# LDA_Board.net
KiCad netlist of a schematic drawn in EAGLE
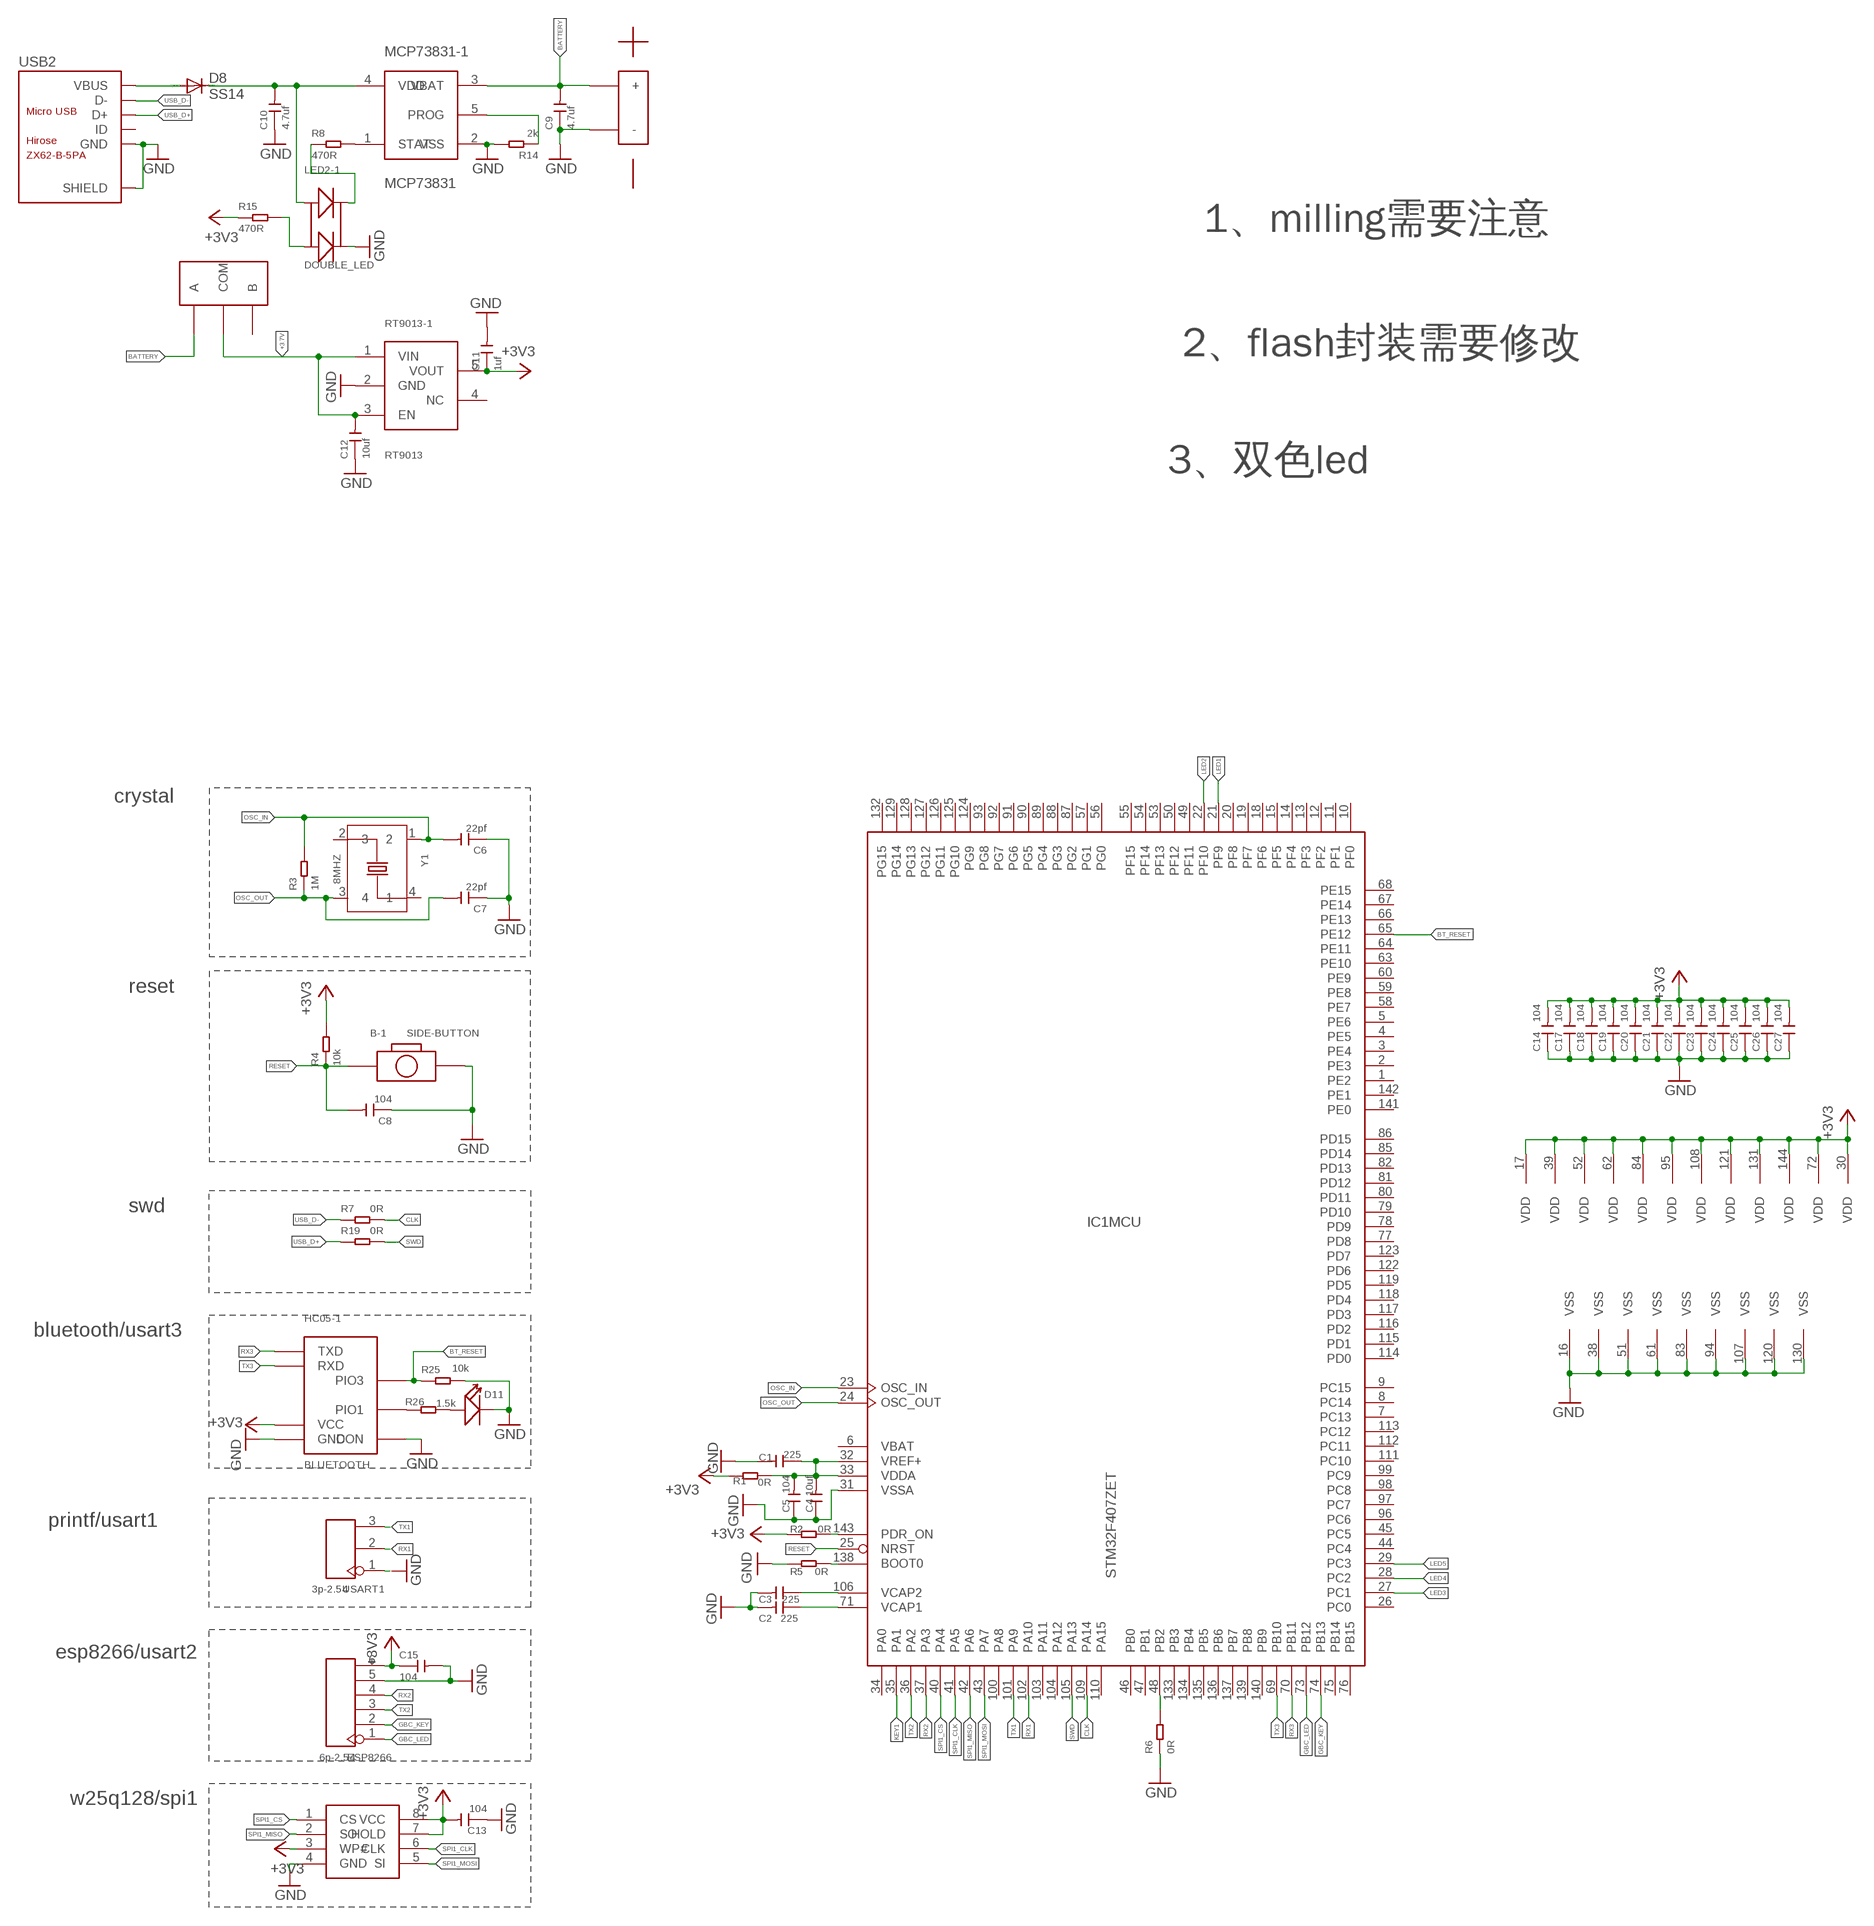
[diagram p0: schematic, sheet 1, part 1 of 2]
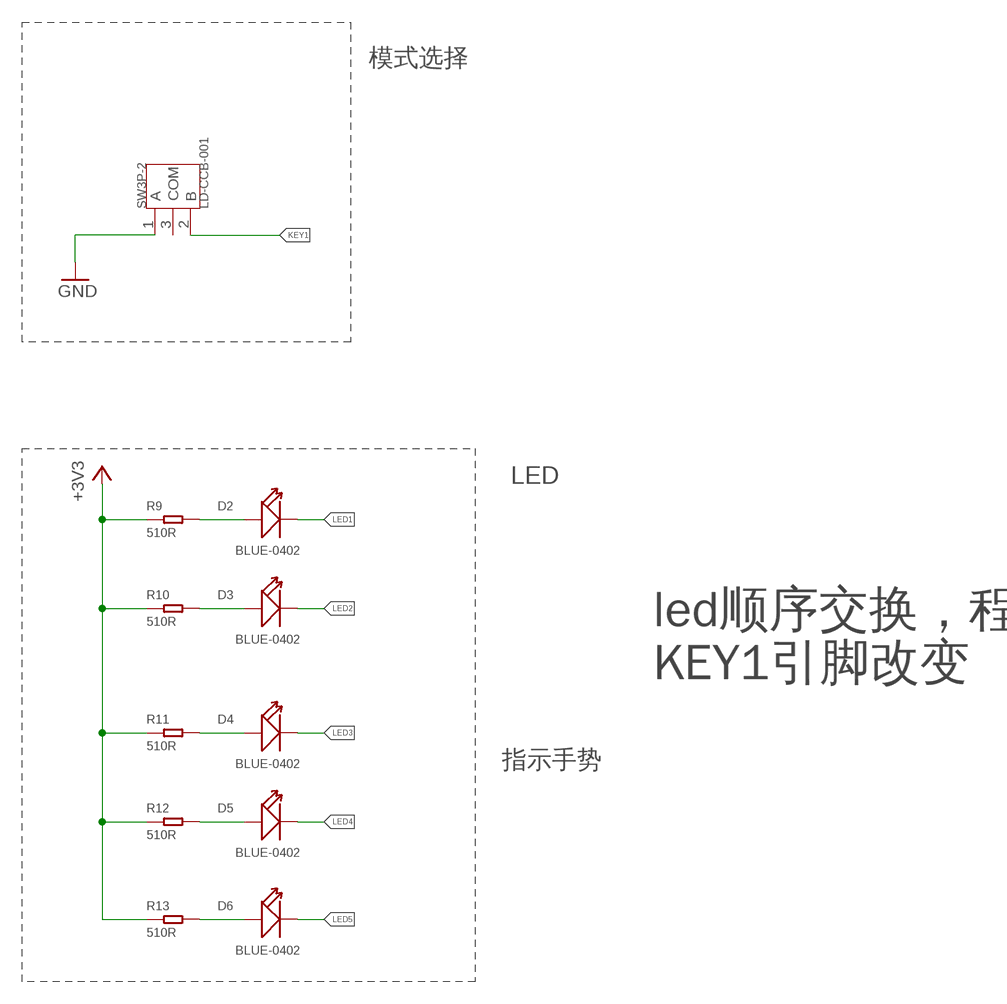
[diagram p1: schematic, sheet 1, part 2 of 2]

(export (version "E")
  (design (tool "Eeschema 10.0.6"))
  (components
    (comp (ref "B-1")
      (value "SIDE-BUTTON")
      (footprint "eagle-import:SIDE-BUTTON")
      (libsource (lib "eagle-import") (part "SIDE-BUTTON"))
    )
    (comp (ref "BATTERY-1")
      (value "BATTERY")
      (footprint "eagle-import:BATTERY")
      (libsource (lib "eagle-import") (part "BATTERY"))
    )
    (comp (ref "C1")
      (value "225")
      (footprint "eagle-import:C0402")
      (fields (field (name "MPN") "GRM1555C1H150JA01D"))
      (libsource (lib "eagle-import") (part "CAP-(0402)"))
    )
    (comp (ref "C2")
      (value "225")
      (footprint "eagle-import:C0402")
      (fields (field (name "MPN") "GRM1555C1H150JA01D"))
      (libsource (lib "eagle-import") (part "CAP-(0402)"))
    )
    (comp (ref "C3")
      (value "225")
      (footprint "eagle-import:C0402")
      (fields (field (name "MPN") "GRM1555C1H150JA01D"))
      (libsource (lib "eagle-import") (part "CAP-(0402)"))
    )
    (comp (ref "C4")
      (value "10uf")
      (footprint "eagle-import:C0402")
      (fields (field (name "MPN") "GRM1555C1H150JA01D"))
      (libsource (lib "eagle-import") (part "CAP-(0402)"))
    )
    (comp (ref "C5")
      (value "104")
      (footprint "eagle-import:C0402")
      (fields (field (name "MPN") "GRM1555C1H150JA01D"))
      (libsource (lib "eagle-import") (part "CAP-(0402)"))
    )
    (comp (ref "C6")
      (value "22pf")
      (footprint "eagle-import:C0402")
      (fields (field (name "MPN") "GRM1555C1H150JA01D"))
      (libsource (lib "eagle-import") (part "CAP-(0402)"))
    )
    (comp (ref "C7")
      (value "22pf")
      (footprint "eagle-import:C0402")
      (fields (field (name "MPN") "GRM1555C1H150JA01D"))
      (libsource (lib "eagle-import") (part "CAP-(0402)"))
    )
    (comp (ref "C8")
      (value "104")
      (footprint "eagle-import:C0402")
      (fields (field (name "MPN") "GRM1555C1H150JA01D"))
      (libsource (lib "eagle-import") (part "CAP-(0402)"))
    )
    (comp (ref "C9")
      (value "4.7uf")
      (footprint "eagle-import:C0402")
      (fields (field (name "MPN") "GRM1555C1H150JA01D"))
      (libsource (lib "eagle-import") (part "CAP-(0402)"))
    )
    (comp (ref "C10")
      (value "4.7uf")
      (footprint "eagle-import:C0402")
      (fields (field (name "MPN") "GRM1555C1H150JA01D"))
      (libsource (lib "eagle-import") (part "CAP-(0402)"))
    )
    (comp (ref "C11")
      (value "1uf")
      (footprint "eagle-import:C0402")
      (fields (field (name "MPN") "GRM1555C1H150JA01D"))
      (libsource (lib "eagle-import") (part "CAP-(0402)"))
    )
    (comp (ref "C12")
      (value "10uf")
      (footprint "eagle-import:C0402")
      (fields (field (name "MPN") "GRM1555C1H150JA01D"))
      (libsource (lib "eagle-import") (part "CAP-(0402)"))
    )
    (comp (ref "C13")
      (value "104")
      (footprint "eagle-import:C0402")
      (fields (field (name "MPN") "GRM1555C1H150JA01D"))
      (libsource (lib "eagle-import") (part "CAP-(0402)"))
    )
    (comp (ref "C14")
      (value "104")
      (footprint "eagle-import:C0402")
      (fields (field (name "MPN") "GRM1555C1H150JA01D"))
      (libsource (lib "eagle-import") (part "CAP-(0402)"))
    )
    (comp (ref "C15")
      (value "104")
      (footprint "eagle-import:C0402")
      (fields (field (name "MPN") "GRM1555C1H150JA01D"))
      (libsource (lib "eagle-import") (part "CAP-(0402)"))
    )
    (comp (ref "C17")
      (value "104")
      (footprint "eagle-import:C0402")
      (fields (field (name "MPN") "GRM1555C1H150JA01D"))
      (libsource (lib "eagle-import") (part "CAP-(0402)"))
    )
    (comp (ref "C18")
      (value "104")
      (footprint "eagle-import:C0402")
      (fields (field (name "MPN") "GRM1555C1H150JA01D"))
      (libsource (lib "eagle-import") (part "CAP-(0402)"))
    )
    (comp (ref "C19")
      (value "104")
      (footprint "eagle-import:C0402")
      (fields (field (name "MPN") "GRM1555C1H150JA01D"))
      (libsource (lib "eagle-import") (part "CAP-(0402)"))
    )
    (comp (ref "C20")
      (value "104")
      (footprint "eagle-import:C0402")
      (fields (field (name "MPN") "GRM1555C1H150JA01D"))
      (libsource (lib "eagle-import") (part "CAP-(0402)"))
    )
    (comp (ref "C21")
      (value "104")
      (footprint "eagle-import:C0402")
      (fields (field (name "MPN") "GRM1555C1H150JA01D"))
      (libsource (lib "eagle-import") (part "CAP-(0402)"))
    )
    (comp (ref "C22")
      (value "104")
      (footprint "eagle-import:C0402")
      (fields (field (name "MPN") "GRM1555C1H150JA01D"))
      (libsource (lib "eagle-import") (part "CAP-(0402)"))
    )
    (comp (ref "C23")
      (value "104")
      (footprint "eagle-import:C0402")
      (fields (field (name "MPN") "GRM1555C1H150JA01D"))
      (libsource (lib "eagle-import") (part "CAP-(0402)"))
    )
    (comp (ref "C24")
      (value "104")
      (footprint "eagle-import:C0402")
      (fields (field (name "MPN") "GRM1555C1H150JA01D"))
      (libsource (lib "eagle-import") (part "CAP-(0402)"))
    )
    (comp (ref "C25")
      (value "104")
      (footprint "eagle-import:C0402")
      (fields (field (name "MPN") "GRM1555C1H150JA01D"))
      (libsource (lib "eagle-import") (part "CAP-(0402)"))
    )
    (comp (ref "C26")
      (value "104")
      (footprint "eagle-import:C0402")
      (fields (field (name "MPN") "GRM1555C1H150JA01D"))
      (libsource (lib "eagle-import") (part "CAP-(0402)"))
    )
    (comp (ref "C27")
      (value "104")
      (footprint "eagle-import:C0402")
      (fields (field (name "MPN") "GRM1555C1H150JA01D"))
      (libsource (lib "eagle-import") (part "CAP-(0402)"))
    )
    (comp (ref "D2")
      (value "BLUE-0402")
      (footprint "eagle-import:LED-0402")
      (fields (field (name "MPN") "BL-HB337A-AV-TRB"))
      (libsource (lib "eagle-import") (part "LED-(0402)"))
    )
    (comp (ref "D3")
      (value "BLUE-0402")
      (footprint "eagle-import:LED-0402")
      (fields (field (name "MPN") "BL-HB337A-AV-TRB"))
      (libsource (lib "eagle-import") (part "LED-(0402)"))
    )
    (comp (ref "D4")
      (value "BLUE-0402")
      (footprint "eagle-import:LED-0402")
      (fields (field (name "MPN") "BL-HB337A-AV-TRB"))
      (libsource (lib "eagle-import") (part "LED-(0402)"))
    )
    (comp (ref "D5")
      (value "BLUE-0402")
      (footprint "eagle-import:LED-0402")
      (fields (field (name "MPN") "BL-HB337A-AV-TRB"))
      (libsource (lib "eagle-import") (part "LED-(0402)"))
    )
    (comp (ref "D6")
      (value "BLUE-0402")
      (footprint "eagle-import:LED-0402")
      (fields (field (name "MPN") "BL-HB337A-AV-TRB"))
      (libsource (lib "eagle-import") (part "LED-(0402)"))
    )
    (comp (ref "D8")
      (value "SS14")
      (footprint "eagle-import:SMA")
      (libsource (lib "eagle-import") (part "SS14"))
    )
    (comp (ref "D11")
      (value "BLUE-0402")
      (footprint "eagle-import:LED-0402")
      (fields (field (name "MPN") "BL-HB337A-AV-TRB"))
      (libsource (lib "eagle-import") (part "LED-(0402)"))
    )
    (comp (ref "ESP8266")
      (value "6p-2.54")
      (footprint "eagle-import:H6-2.54")
      (fields (field (name "MPN") "F185-1106A1BSYC1"))
      (libsource (lib "eagle-import") (part "DIP-BLACK-FEMALE-HEADER-VERT(6P-2.54)"))
    )
    (comp (ref "HC05-1")
      (value "BLUETOOTH")
      (footprint "eagle-import:BLUETOOTH")
      (libsource (lib "eagle-import") (part "BLUETOOTH"))
    )
    (comp (ref "IC1")
      (value "STM32F407ZET")
      (footprint "eagle-import:LQFP144")
      (libsource (lib "eagle-import") (part "STM32F407ZTE"))
    )
    (comp (ref "LED2-1")
      (value "DOUBLE_LED")
      (footprint "eagle-import:LED2-SMD-1010")
      (libsource (lib "eagle-import") (part "DOUBLE_LED"))
    )
    (comp (ref "MCP73831-1")
      (value "MCP73831")
      (footprint "eagle-import:SOT23-5")
      (libsource (lib "eagle-import") (part "MCP73831"))
    )
    (comp (ref "R1")
      (value "0R")
      (footprint "eagle-import:R0402")
      (fields (field (name "MPN") "RC0402JR-070RL"))
      (libsource (lib "eagle-import") (part "RES-(0402)"))
    )
    (comp (ref "R2")
      (value "0R")
      (footprint "eagle-import:R0402")
      (fields (field (name "MPN") "RC0402JR-070RL"))
      (libsource (lib "eagle-import") (part "RES-(0402)"))
    )
    (comp (ref "R3")
      (value "1M")
      (footprint "eagle-import:R0402")
      (fields (field (name "MPN") "RC0402JR-070RL"))
      (libsource (lib "eagle-import") (part "RES-(0402)"))
    )
    (comp (ref "R4")
      (value "10k")
      (footprint "eagle-import:R0402")
      (fields (field (name "MPN") "RC0402JR-070RL"))
      (libsource (lib "eagle-import") (part "RES-(0402)"))
    )
    (comp (ref "R5")
      (value "0R")
      (footprint "eagle-import:R0402")
      (fields (field (name "MPN") "RC0402JR-070RL"))
      (libsource (lib "eagle-import") (part "RES-(0402)"))
    )
    (comp (ref "R6")
      (value "0R")
      (footprint "eagle-import:R0402")
      (fields (field (name "MPN") "RC0402JR-070RL"))
      (libsource (lib "eagle-import") (part "RES-(0402)"))
    )
    (comp (ref "R7")
      (value "0R")
      (footprint "eagle-import:R0402")
      (fields (field (name "MPN") "RC0402JR-070RL"))
      (libsource (lib "eagle-import") (part "RES-(0402)"))
    )
    (comp (ref "R8")
      (value "470R")
      (footprint "eagle-import:R0402")
      (fields (field (name "MPN") "RC0402JR-070RL"))
      (libsource (lib "eagle-import") (part "RES-(0402)"))
    )
    (comp (ref "R9")
      (value "510R")
      (footprint "eagle-import:R0402")
      (fields (field (name "MPN") "RC0402JR-070RL"))
      (libsource (lib "eagle-import") (part "RES-(0402)"))
    )
    (comp (ref "R10")
      (value "510R")
      (footprint "eagle-import:R0402")
      (fields (field (name "MPN") "RC0402JR-070RL"))
      (libsource (lib "eagle-import") (part "RES-(0402)"))
    )
    (comp (ref "R11")
      (value "510R")
      (footprint "eagle-import:R0402")
      (fields (field (name "MPN") "RC0402JR-070RL"))
      (libsource (lib "eagle-import") (part "RES-(0402)"))
    )
    (comp (ref "R12")
      (value "510R")
      (footprint "eagle-import:R0402")
      (fields (field (name "MPN") "RC0402JR-070RL"))
      (libsource (lib "eagle-import") (part "RES-(0402)"))
    )
    (comp (ref "R13")
      (value "510R")
      (footprint "eagle-import:R0402")
      (fields (field (name "MPN") "RC0402JR-070RL"))
      (libsource (lib "eagle-import") (part "RES-(0402)"))
    )
    (comp (ref "R14")
      (value "2k")
      (footprint "eagle-import:R0402")
      (fields (field (name "MPN") "RC0402JR-070RL"))
      (libsource (lib "eagle-import") (part "RES-(0402)"))
    )
    (comp (ref "R15")
      (value "470R")
      (footprint "eagle-import:R0402")
      (fields (field (name "MPN") "RC0402JR-070RL"))
      (libsource (lib "eagle-import") (part "RES-(0402)"))
    )
    (comp (ref "R19")
      (value "0R")
      (footprint "eagle-import:R0402")
      (fields (field (name "MPN") "RC0402JR-070RL"))
      (libsource (lib "eagle-import") (part "RES-(0402)"))
    )
    (comp (ref "R25")
      (value "10k")
      (footprint "eagle-import:R0402")
      (fields (field (name "MPN") "RC0402JR-070RL"))
      (libsource (lib "eagle-import") (part "RES-(0402)"))
    )
    (comp (ref "R26")
      (value "1.5k")
      (footprint "eagle-import:R0402")
      (fields (field (name "MPN") "RC0402JR-070RL"))
      (libsource (lib "eagle-import") (part "RES-(0402)"))
    )
    (comp (ref "RT9013-1")
      (value "RT9013")
      (footprint "eagle-import:SOT23-5")
      (libsource (lib "eagle-import") (part "RT9013"))
    )
    (comp (ref "SW-1")
      (value "SWITCH-3P")
      (footprint "eagle-import:SWITCH-3P")
      (libsource (lib "eagle-import") (part "SWITCH-3P"))
    )
    (comp (ref "SW3P-2")
      (value "LD-CCB-001")
      (footprint "eagle-import:SW3-2.54-9.0X3.5X3.5+2.0MM")
      (libsource (lib "eagle-import") (part "SWITCH(3P)"))
    )
    (comp (ref "USART1")
      (value "3p-2.54")
      (footprint "eagle-import:H3-2.54")
      (fields (field (name "MPN") "F185-1103A0BSYA1"))
      (libsource (lib "eagle-import") (part "DIP-BLACK-FEMALE-HEADER-VERT(3P-2.54)"))
    )
    (comp (ref "USB2")
      (value "ZX62-B-5PA")
      (footprint "eagle-import:MICRO-USB5+6P-SMD-0.65-AB")
      (libsource (lib "eagle-import") (part "MICRO-USB-SMD(ZX62-B-5PA)"))
    )
    (comp (ref "W25Q128")
      (value "W25Q128")
      (footprint "eagle-import:SOP08")
      (libsource (lib "eagle-import") (part "W25Q128"))
    )
    (comp (ref "Y1")
      (value "8MHZ")
      (footprint "eagle-import:X4-SMD-3.2X2.5X0.7MM")
      (fields (field (name "MPN") "7M-27.120MAAJ-T"))
      (libsource (lib "eagle-import") (part "SMD-CRYSTAL-27.12MHZ-18PF-30PPM-60R(4P-3.2X2.5MM)"))
    )
  )
  (nets
    (net (code "1") (name "+3.7V") (class "Default")
      (node (ref "C12") (pin "2") (pinfunction "2_2") (pintype "passive"))
      (node (ref "RT9013-1") (pin "1") (pinfunction "VIN_1") (pintype "bidirectional"))
      (node (ref "RT9013-1") (pin "3") (pinfunction "EN_3") (pintype "bidirectional"))
      (node (ref "SW-1") (pin "P$2") (pinfunction "COM_P$2") (pintype "bidirectional"))
    )
    (net (code "2") (name "+3V3") (class "Default")
      (node (ref "C11") (pin "1") (pinfunction "1_1") (pintype "passive"))
      (node (ref "C13") (pin "2") (pinfunction "2_2") (pintype "passive"))
      (node (ref "C14") (pin "2") (pinfunction "2_2") (pintype "passive"))
      (node (ref "C15") (pin "1") (pinfunction "1_1") (pintype "passive"))
      (node (ref "C17") (pin "2") (pinfunction "2_2") (pintype "passive"))
      (node (ref "C18") (pin "2") (pinfunction "2_2") (pintype "passive"))
      (node (ref "C19") (pin "2") (pinfunction "2_2") (pintype "passive"))
      (node (ref "C20") (pin "2") (pinfunction "2_2") (pintype "passive"))
      (node (ref "C21") (pin "2") (pinfunction "2_2") (pintype "passive"))
      (node (ref "C22") (pin "2") (pinfunction "2_2") (pintype "passive"))
      (node (ref "C23") (pin "2") (pinfunction "2_2") (pintype "passive"))
      (node (ref "C24") (pin "2") (pinfunction "2_2") (pintype "passive"))
      (node (ref "C25") (pin "2") (pinfunction "2_2") (pintype "passive"))
      (node (ref "C26") (pin "2") (pinfunction "2_2") (pintype "passive"))
      (node (ref "C27") (pin "2") (pinfunction "2_2") (pintype "passive"))
      (node (ref "ESP8266") (pin "6") (pinfunction "6_6") (pintype "bidirectional"))
      (node (ref "HC05-1") (pin "P$12") (pinfunction "VCC_P$12") (pintype "bidirectional"))
      (node (ref "IC1") (pin "108") (pinfunction "VDD_108") (pintype "power_in"))
      (node (ref "IC1") (pin "121") (pinfunction "VDD_121") (pintype "power_in"))
      (node (ref "IC1") (pin "131") (pinfunction "VDD_131") (pintype "power_in"))
      (node (ref "IC1") (pin "144") (pinfunction "VDD_144") (pintype "power_in"))
      (node (ref "IC1") (pin "17") (pinfunction "VDD_17") (pintype "power_in"))
      (node (ref "IC1") (pin "30") (pinfunction "VDD_30") (pintype "power_in"))
      (node (ref "IC1") (pin "39") (pinfunction "VDD_39") (pintype "power_in"))
      (node (ref "IC1") (pin "52") (pinfunction "VDD_52") (pintype "power_in"))
      (node (ref "IC1") (pin "62") (pinfunction "VDD_62") (pintype "power_in"))
      (node (ref "IC1") (pin "72") (pinfunction "VDD_72") (pintype "power_in"))
      (node (ref "IC1") (pin "84") (pinfunction "VDD_84") (pintype "power_in"))
      (node (ref "IC1") (pin "95") (pinfunction "VDD_95") (pintype "power_in"))
      (node (ref "R1") (pin "1") (pinfunction "1_1") (pintype "passive"))
      (node (ref "R10") (pin "1") (pinfunction "1_1") (pintype "passive"))
      (node (ref "R11") (pin "1") (pinfunction "1_1") (pintype "passive"))
      (node (ref "R12") (pin "1") (pinfunction "1_1") (pintype "passive"))
      (node (ref "R13") (pin "1") (pinfunction "1_1") (pintype "passive"))
      (node (ref "R15") (pin "1") (pinfunction "1_1") (pintype "passive"))
      (node (ref "R2") (pin "1") (pinfunction "1_1") (pintype "passive"))
      (node (ref "R4") (pin "2") (pinfunction "2_2") (pintype "passive"))
      (node (ref "R9") (pin "1") (pinfunction "1_1") (pintype "passive"))
      (node (ref "RT9013-1") (pin "5") (pinfunction "VOUT_5") (pintype "bidirectional"))
      (node (ref "W25Q128") (pin "3") (pinfunction "WP#_3") (pintype "bidirectional"))
      (node (ref "W25Q128") (pin "7") (pinfunction "HOLD_7") (pintype "bidirectional"))
      (node (ref "W25Q128") (pin "8") (pinfunction "VCC_8") (pintype "bidirectional"))
    )
    (net (code "3") (name "/VBAT") (class "Default")
      (node (ref "IC1") (pin "6") (pinfunction "VBAT_6") (pintype "power_in"))
    )
    (net (code "4") (name "BATTERY") (class "Default")
      (node (ref "BATTERY-1") (pin "P$1") (pinfunction "+_P$1") (pintype "bidirectional"))
      (node (ref "C9") (pin "2") (pinfunction "2_2") (pintype "passive"))
      (node (ref "MCP73831-1") (pin "3") (pinfunction "VBAT_3") (pintype "bidirectional"))
      (node (ref "SW-1") (pin "P$3") (pinfunction "A_P$3") (pintype "bidirectional"))
    )
    (net (code "5") (name "BT_RESET") (class "Default")
      (node (ref "HC05-1") (pin "P$26") (pinfunction "PIO3_P$26") (pintype "bidirectional"))
      (node (ref "IC1") (pin "65") (pinfunction "PE12_65") (pintype "bidirectional"))
      (node (ref "R25") (pin "1") (pinfunction "1_1") (pintype "passive"))
    )
    (net (code "6") (name "CLK") (class "Default")
      (node (ref "IC1") (pin "109") (pinfunction "PA14_109") (pintype "bidirectional"))
      (node (ref "R7") (pin "2") (pinfunction "2_2") (pintype "passive"))
    )
    (net (code "7") (name "GBC_KEY") (class "Default")
      (node (ref "ESP8266") (pin "2") (pinfunction "2_2") (pintype "bidirectional"))
      (node (ref "IC1") (pin "74") (pinfunction "PB13_74") (pintype "bidirectional"))
    )
    (net (code "8") (name "GBC_LED") (class "Default")
      (node (ref "ESP8266") (pin "1") (pinfunction "1_1") (pintype "bidirectional"))
      (node (ref "IC1") (pin "73") (pinfunction "PB12_73") (pintype "bidirectional"))
    )
    (net (code "9") (name "GND") (class "Default")
      (node (ref "B-1") (pin "P$1") (pinfunction "2_P$1") (pintype "bidirectional"))
      (node (ref "BATTERY-1") (pin "P$2") (pinfunction "-_P$2") (pintype "bidirectional"))
      (node (ref "C1") (pin "2") (pinfunction "2_2") (pintype "passive"))
      (node (ref "C10") (pin "1") (pinfunction "1_1") (pintype "passive"))
      (node (ref "C11") (pin "2") (pinfunction "2_2") (pintype "passive"))
      (node (ref "C12") (pin "1") (pinfunction "1_1") (pintype "passive"))
      (node (ref "C13") (pin "1") (pinfunction "1_1") (pintype "passive"))
      (node (ref "C14") (pin "1") (pinfunction "1_1") (pintype "passive"))
      (node (ref "C15") (pin "2") (pinfunction "2_2") (pintype "passive"))
      (node (ref "C17") (pin "1") (pinfunction "1_1") (pintype "passive"))
      (node (ref "C18") (pin "1") (pinfunction "1_1") (pintype "passive"))
      (node (ref "C19") (pin "1") (pinfunction "1_1") (pintype "passive"))
      (node (ref "C2") (pin "2") (pinfunction "2_2") (pintype "passive"))
      (node (ref "C20") (pin "1") (pinfunction "1_1") (pintype "passive"))
      (node (ref "C21") (pin "1") (pinfunction "1_1") (pintype "passive"))
      (node (ref "C22") (pin "1") (pinfunction "1_1") (pintype "passive"))
      (node (ref "C23") (pin "1") (pinfunction "1_1") (pintype "passive"))
      (node (ref "C24") (pin "1") (pinfunction "1_1") (pintype "passive"))
      (node (ref "C25") (pin "1") (pinfunction "1_1") (pintype "passive"))
      (node (ref "C26") (pin "1") (pinfunction "1_1") (pintype "passive"))
      (node (ref "C27") (pin "1") (pinfunction "1_1") (pintype "passive"))
      (node (ref "C3") (pin "2") (pinfunction "2_2") (pintype "passive"))
      (node (ref "C4") (pin "1") (pinfunction "1_1") (pintype "passive"))
      (node (ref "C5") (pin "1") (pinfunction "1_1") (pintype "passive"))
      (node (ref "C6") (pin "1") (pinfunction "1_1") (pintype "passive"))
      (node (ref "C7") (pin "1") (pinfunction "1_1") (pintype "passive"))
      (node (ref "C8") (pin "1") (pinfunction "1_1") (pintype "passive"))
      (node (ref "C9") (pin "1") (pinfunction "1_1") (pintype "passive"))
      (node (ref "D11") (pin "-") (pinfunction "-_-") (pintype "passive"))
      (node (ref "ESP8266") (pin "5") (pinfunction "5_5") (pintype "bidirectional"))
      (node (ref "HC05-1") (pin "P$13") (pinfunction "GND_P$13") (pintype "bidirectional"))
      (node (ref "HC05-1") (pin "P$22") (pinfunction "CON_P$22") (pintype "bidirectional"))
      (node (ref "IC1") (pin "107") (pinfunction "VSS_107") (pintype "power_in"))
      (node (ref "IC1") (pin "120") (pinfunction "VSS_120") (pintype "power_in"))
      (node (ref "IC1") (pin "130") (pinfunction "VSS_130") (pintype "power_in"))
      (node (ref "IC1") (pin "16") (pinfunction "VSS_16") (pintype "power_in"))
      (node (ref "IC1") (pin "31") (pinfunction "VSSA_31") (pintype "power_in"))
      (node (ref "IC1") (pin "38") (pinfunction "VSS_38") (pintype "power_in"))
      (node (ref "IC1") (pin "51") (pinfunction "VSS_51") (pintype "power_in"))
      (node (ref "IC1") (pin "61") (pinfunction "VSS_61") (pintype "power_in"))
      (node (ref "IC1") (pin "83") (pinfunction "VSS_83") (pintype "power_in"))
      (node (ref "IC1") (pin "94") (pinfunction "VSS_94") (pintype "power_in"))
      (node (ref "LED2-1") (pin "3") (pinfunction "3_3") (pintype "passive"))
      (node (ref "MCP73831-1") (pin "2") (pinfunction "VSS_2") (pintype "bidirectional"))
      (node (ref "R14") (pin "2") (pinfunction "2_2") (pintype "passive"))
      (node (ref "R25") (pin "2") (pinfunction "2_2") (pintype "passive"))
      (node (ref "R5") (pin "1") (pinfunction "1_1") (pintype "passive"))
      (node (ref "R6") (pin "1") (pinfunction "1_1") (pintype "passive"))
      (node (ref "RT9013-1") (pin "2") (pinfunction "GND_2") (pintype "bidirectional"))
      (node (ref "SW3P-2") (pin "1") (pinfunction "A_1") (pintype "bidirectional"))
      (node (ref "USART1") (pin "1") (pinfunction "P$1_1") (pintype "bidirectional"))
      (node (ref "USB2") (pin "5") (pinfunction "GND_5") (pintype "power_in"))
      (node (ref "USB2") (pin "P1") (pinfunction "SHIELD_P1") (pintype "power_in"))
      (node (ref "USB2") (pin "P2") (pinfunction "SHIELD_P2") (pintype "power_in"))
      (node (ref "USB2") (pin "P3") (pinfunction "SHIELD_P3") (pintype "power_in"))
      (node (ref "USB2") (pin "P4") (pinfunction "SHIELD_P4") (pintype "power_in"))
      (node (ref "USB2") (pin "P5") (pinfunction "SHIELD_P5") (pintype "power_in"))
      (node (ref "USB2") (pin "P6") (pinfunction "SHIELD_P6") (pintype "power_in"))
      (node (ref "W25Q128") (pin "4") (pinfunction "GND_4") (pintype "bidirectional"))
    )
    (net (code "10") (name "KEY1") (class "Default")
      (node (ref "IC1") (pin "35") (pinfunction "PA1_35") (pintype "bidirectional"))
      (node (ref "SW3P-2") (pin "2") (pinfunction "B_2") (pintype "bidirectional"))
    )
    (net (code "11") (name "LED1") (class "Default")
      (node (ref "D2") (pin "-") (pinfunction "-_-") (pintype "passive"))
      (node (ref "IC1") (pin "21") (pinfunction "PF9_21") (pintype "bidirectional"))
    )
    (net (code "12") (name "LED2") (class "Default")
      (node (ref "D3") (pin "-") (pinfunction "-_-") (pintype "passive"))
      (node (ref "IC1") (pin "22") (pinfunction "PF10_22") (pintype "bidirectional"))
    )
    (net (code "13") (name "LED3") (class "Default")
      (node (ref "D4") (pin "-") (pinfunction "-_-") (pintype "passive"))
      (node (ref "IC1") (pin "27") (pinfunction "PC1_27") (pintype "bidirectional"))
    )
    (net (code "14") (name "LED4") (class "Default")
      (node (ref "D5") (pin "-") (pinfunction "-_-") (pintype "passive"))
      (node (ref "IC1") (pin "28") (pinfunction "PC2_28") (pintype "bidirectional"))
    )
    (net (code "15") (name "LED5") (class "Default")
      (node (ref "D6") (pin "-") (pinfunction "-_-") (pintype "passive"))
      (node (ref "IC1") (pin "29") (pinfunction "PC3_29") (pintype "bidirectional"))
    )
    (net (code "16") (name "Net-(D2-Pad+)") (class "Default")
      (node (ref "D2") (pin "+") (pinfunction "+_+") (pintype "passive"))
      (node (ref "R9") (pin "2") (pinfunction "2_2") (pintype "passive"))
    )
    (net (code "17") (name "Net-(D3-Pad+)") (class "Default")
      (node (ref "D3") (pin "+") (pinfunction "+_+") (pintype "passive"))
      (node (ref "R10") (pin "2") (pinfunction "2_2") (pintype "passive"))
    )
    (net (code "18") (name "Net-(D4-Pad+)") (class "Default")
      (node (ref "D4") (pin "+") (pinfunction "+_+") (pintype "passive"))
      (node (ref "R11") (pin "2") (pinfunction "2_2") (pintype "passive"))
    )
    (net (code "19") (name "Net-(D5-Pad+)") (class "Default")
      (node (ref "D5") (pin "+") (pinfunction "+_+") (pintype "passive"))
      (node (ref "R12") (pin "2") (pinfunction "2_2") (pintype "passive"))
    )
    (net (code "20") (name "Net-(D6-Pad+)") (class "Default")
      (node (ref "D6") (pin "+") (pinfunction "+_+") (pintype "passive"))
      (node (ref "R13") (pin "2") (pinfunction "2_2") (pintype "passive"))
    )
    (net (code "21") (name "Net-(D11-Pad+)") (class "Default")
      (node (ref "D11") (pin "+") (pinfunction "+_+") (pintype "passive"))
      (node (ref "R26") (pin "2") (pinfunction "2_2") (pintype "passive"))
    )
    (net (code "22") (name "Net-(HC05-1-PIO1)") (class "Default")
      (node (ref "HC05-1") (pin "P$24") (pinfunction "PIO1_P$24") (pintype "bidirectional"))
      (node (ref "R26") (pin "1") (pinfunction "1_1") (pintype "passive"))
    )
    (net (code "23") (name "Net-(IC1A-BOOT0)") (class "Default")
      (node (ref "IC1") (pin "138") (pinfunction "BOOT0_138") (pintype "input"))
      (node (ref "R5") (pin "2") (pinfunction "2_2") (pintype "passive"))
    )
    (net (code "24") (name "Net-(IC1A-PB2)") (class "Default")
      (node (ref "IC1") (pin "48") (pinfunction "PB2_48") (pintype "bidirectional"))
      (node (ref "R6") (pin "2") (pinfunction "2_2") (pintype "passive"))
    )
    (net (code "25") (name "Net-(IC1A-PDR_ON)") (class "Default")
      (node (ref "IC1") (pin "143") (pinfunction "PDR_ON_143") (pintype "input"))
      (node (ref "R2") (pin "2") (pinfunction "2_2") (pintype "passive"))
    )
    (net (code "26") (name "Net-(IC1A-VCAP1)") (class "Default")
      (node (ref "C2") (pin "1") (pinfunction "1_1") (pintype "passive"))
      (node (ref "IC1") (pin "71") (pinfunction "VCAP1_71") (pintype "power_in"))
    )
    (net (code "27") (name "Net-(IC1A-VCAP2)") (class "Default")
      (node (ref "C3") (pin "1") (pinfunction "1_1") (pintype "passive"))
      (node (ref "IC1") (pin "106") (pinfunction "VCAP2_106") (pintype "power_in"))
    )
    (net (code "28") (name "Net-(IC1A-VDDA)") (class "Default")
      (node (ref "C1") (pin "1") (pinfunction "1_1") (pintype "passive"))
      (node (ref "C4") (pin "2") (pinfunction "2_2") (pintype "passive"))
      (node (ref "C5") (pin "2") (pinfunction "2_2") (pintype "passive"))
      (node (ref "IC1") (pin "32") (pinfunction "VREF+_32") (pintype "power_in"))
      (node (ref "IC1") (pin "33") (pinfunction "VDDA_33") (pintype "power_in"))
      (node (ref "R1") (pin "2") (pinfunction "2_2") (pintype "passive"))
    )
    (net (code "29") (name "Net-(LED2-1-Pad2)") (class "Default")
      (node (ref "LED2-1") (pin "2") (pinfunction "2_2") (pintype "passive"))
      (node (ref "R15") (pin "2") (pinfunction "2_2") (pintype "passive"))
    )
    (net (code "30") (name "Net-(LED2-1-Pad4)") (class "Default")
      (node (ref "LED2-1") (pin "4") (pinfunction "4_4") (pintype "passive"))
      (node (ref "R8") (pin "1") (pinfunction "1_1") (pintype "passive"))
    )
    (net (code "31") (name "Net-(MCP73831-1-PROG)") (class "Default")
      (node (ref "MCP73831-1") (pin "5") (pinfunction "PROG_5") (pintype "bidirectional"))
      (node (ref "R14") (pin "1") (pinfunction "1_1") (pintype "passive"))
    )
    (net (code "32") (name "Net-(MCP73831-1-STAT)") (class "Default")
      (node (ref "MCP73831-1") (pin "1") (pinfunction "STAT_1") (pintype "bidirectional"))
      (node (ref "R8") (pin "2") (pinfunction "2_2") (pintype "passive"))
    )
    (net (code "33") (name "Net-(MCP73831-1-VDD)") (class "Default")
      (node (ref "C10") (pin "2") (pinfunction "2_2") (pintype "passive"))
      (node (ref "D8") (pin "C") (pinfunction "C_C") (pintype "passive"))
      (node (ref "LED2-1") (pin "1") (pinfunction "1_1") (pintype "passive"))
      (node (ref "MCP73831-1") (pin "4") (pinfunction "VDD_4") (pintype "bidirectional"))
    )
    (net (code "34") (name "Net-(USB2-VBUS)") (class "Default")
      (node (ref "D8") (pin "A") (pinfunction "A_A") (pintype "passive"))
      (node (ref "USB2") (pin "1") (pinfunction "VBUS_1") (pintype "power_in"))
    )
    (net (code "35") (name "OSC_IN") (class "Default")
      (node (ref "C6") (pin "2") (pinfunction "2_2") (pintype "passive"))
      (node (ref "IC1") (pin "23") (pinfunction "OSC_IN_23") (pintype "bidirectional"))
      (node (ref "R3") (pin "2") (pinfunction "2_2") (pintype "passive"))
      (node (ref "Y1") (pin "1") (pinfunction "2_1") (pintype "bidirectional"))
    )
    (net (code "36") (name "OSC_OUT") (class "Default")
      (node (ref "C7") (pin "2") (pinfunction "2_2") (pintype "passive"))
      (node (ref "IC1") (pin "24") (pinfunction "OSC_OUT_24") (pintype "bidirectional"))
      (node (ref "R3") (pin "1") (pinfunction "1_1") (pintype "passive"))
      (node (ref "Y1") (pin "3") (pinfunction "4_3") (pintype "bidirectional"))
    )
    (net (code "37") (name "RESET") (class "Default")
      (node (ref "B-1") (pin "P$2") (pinfunction "1_P$2") (pintype "bidirectional"))
      (node (ref "C8") (pin "2") (pinfunction "2_2") (pintype "passive"))
      (node (ref "IC1") (pin "25") (pinfunction "NRST_25") (pintype "bidirectional"))
      (node (ref "R4") (pin "1") (pinfunction "1_1") (pintype "passive"))
    )
    (net (code "38") (name "RX1") (class "Default")
      (node (ref "IC1") (pin "102") (pinfunction "PA10_102") (pintype "bidirectional"))
      (node (ref "USART1") (pin "2") (pinfunction "P$2_2") (pintype "bidirectional"))
    )
    (net (code "39") (name "RX2") (class "Default")
      (node (ref "ESP8266") (pin "4") (pinfunction "4_4") (pintype "bidirectional"))
      (node (ref "IC1") (pin "37") (pinfunction "PA3_37") (pintype "bidirectional"))
    )
    (net (code "40") (name "RX3") (class "Default")
      (node (ref "HC05-1") (pin "P$1") (pinfunction "TXD_P$1") (pintype "bidirectional"))
      (node (ref "IC1") (pin "70") (pinfunction "PB11_70") (pintype "bidirectional"))
    )
    (net (code "41") (name "SPI1_CLK") (class "Default")
      (node (ref "IC1") (pin "41") (pinfunction "PA5_41") (pintype "bidirectional"))
      (node (ref "W25Q128") (pin "6") (pinfunction "CLK_6") (pintype "bidirectional"))
    )
    (net (code "42") (name "SPI1_CS") (class "Default")
      (node (ref "IC1") (pin "40") (pinfunction "PA4_40") (pintype "bidirectional"))
      (node (ref "W25Q128") (pin "1") (pinfunction "CS_1") (pintype "bidirectional"))
    )
    (net (code "43") (name "SPI1_MISO") (class "Default")
      (node (ref "IC1") (pin "42") (pinfunction "PA6_42") (pintype "bidirectional"))
      (node (ref "W25Q128") (pin "2") (pinfunction "SO_2") (pintype "bidirectional"))
    )
    (net (code "44") (name "SPI1_MOSI") (class "Default")
      (node (ref "IC1") (pin "43") (pinfunction "PA7_43") (pintype "bidirectional"))
      (node (ref "W25Q128") (pin "5") (pinfunction "SI_5") (pintype "bidirectional"))
    )
    (net (code "45") (name "SWD") (class "Default")
      (node (ref "IC1") (pin "105") (pinfunction "PA13_105") (pintype "bidirectional"))
      (node (ref "R19") (pin "2") (pinfunction "2_2") (pintype "passive"))
    )
    (net (code "46") (name "TX1") (class "Default")
      (node (ref "IC1") (pin "101") (pinfunction "PA9_101") (pintype "bidirectional"))
      (node (ref "USART1") (pin "3") (pinfunction "P$3_3") (pintype "bidirectional"))
    )
    (net (code "47") (name "TX2") (class "Default")
      (node (ref "ESP8266") (pin "3") (pinfunction "3_3") (pintype "bidirectional"))
      (node (ref "IC1") (pin "36") (pinfunction "PA2_36") (pintype "bidirectional"))
    )
    (net (code "48") (name "TX3") (class "Default")
      (node (ref "HC05-1") (pin "P$2") (pinfunction "RXD_P$2") (pintype "bidirectional"))
      (node (ref "IC1") (pin "69") (pinfunction "PB10_69") (pintype "bidirectional"))
    )
    (net (code "49") (name "USB_D+") (class "Default")
      (node (ref "R19") (pin "1") (pinfunction "1_1") (pintype "passive"))
      (node (ref "USB2") (pin "3") (pinfunction "D+_3") (pintype "bidirectional"))
    )
    (net (code "50") (name "USB_D-") (class "Default")
      (node (ref "R7") (pin "1") (pinfunction "1_1") (pintype "passive"))
      (node (ref "USB2") (pin "2") (pinfunction "D-_2") (pintype "bidirectional"))
    )
    (net (code "51") (name "unconnected-(IC1A-PA0-Pad34)") (class "Default")
      (node (ref "IC1") (pin "34") (pinfunction "PA0_34") (pintype "bidirectional"))
    )
    (net (code "52") (name "unconnected-(IC1A-PA8-Pad100)") (class "Default")
      (node (ref "IC1") (pin "100") (pinfunction "PA8_100") (pintype "bidirectional"))
    )
    (net (code "53") (name "unconnected-(IC1A-PA11-Pad103)") (class "Default")
      (node (ref "IC1") (pin "103") (pinfunction "PA11_103") (pintype "bidirectional"))
    )
    (net (code "54") (name "unconnected-(IC1A-PA12-Pad104)") (class "Default")
      (node (ref "IC1") (pin "104") (pinfunction "PA12_104") (pintype "bidirectional"))
    )
    (net (code "55") (name "unconnected-(IC1A-PA15-Pad110)") (class "Default")
      (node (ref "IC1") (pin "110") (pinfunction "PA15_110") (pintype "bidirectional"))
    )
    (net (code "56") (name "unconnected-(IC1A-PB0-Pad46)") (class "Default")
      (node (ref "IC1") (pin "46") (pinfunction "PB0_46") (pintype "bidirectional"))
    )
    (net (code "57") (name "unconnected-(IC1A-PB1-Pad47)") (class "Default")
      (node (ref "IC1") (pin "47") (pinfunction "PB1_47") (pintype "bidirectional"))
    )
    (net (code "58") (name "unconnected-(IC1A-PB3-Pad133)") (class "Default")
      (node (ref "IC1") (pin "133") (pinfunction "PB3_133") (pintype "bidirectional"))
    )
    (net (code "59") (name "unconnected-(IC1A-PB4-Pad134)") (class "Default")
      (node (ref "IC1") (pin "134") (pinfunction "PB4_134") (pintype "bidirectional"))
    )
    (net (code "60") (name "unconnected-(IC1A-PB5-Pad135)") (class "Default")
      (node (ref "IC1") (pin "135") (pinfunction "PB5_135") (pintype "bidirectional"))
    )
    (net (code "61") (name "unconnected-(IC1A-PB6-Pad136)") (class "Default")
      (node (ref "IC1") (pin "136") (pinfunction "PB6_136") (pintype "bidirectional"))
    )
    (net (code "62") (name "unconnected-(IC1A-PB7-Pad137)") (class "Default")
      (node (ref "IC1") (pin "137") (pinfunction "PB7_137") (pintype "bidirectional"))
    )
    (net (code "63") (name "unconnected-(IC1A-PB8-Pad139)") (class "Default")
      (node (ref "IC1") (pin "139") (pinfunction "PB8_139") (pintype "bidirectional"))
    )
    (net (code "64") (name "unconnected-(IC1A-PB9-Pad140)") (class "Default")
      (node (ref "IC1") (pin "140") (pinfunction "PB9_140") (pintype "bidirectional"))
    )
    (net (code "65") (name "unconnected-(IC1A-PB14-Pad75)") (class "Default")
      (node (ref "IC1") (pin "75") (pinfunction "PB14_75") (pintype "bidirectional"))
    )
    (net (code "66") (name "unconnected-(IC1A-PB15-Pad76)") (class "Default")
      (node (ref "IC1") (pin "76") (pinfunction "PB15_76") (pintype "bidirectional"))
    )
    (net (code "67") (name "unconnected-(IC1A-PC0-Pad26)") (class "Default")
      (node (ref "IC1") (pin "26") (pinfunction "PC0_26") (pintype "bidirectional"))
    )
    (net (code "68") (name "unconnected-(IC1A-PC4-Pad44)") (class "Default")
      (node (ref "IC1") (pin "44") (pinfunction "PC4_44") (pintype "bidirectional"))
    )
    (net (code "69") (name "unconnected-(IC1A-PC5-Pad45)") (class "Default")
      (node (ref "IC1") (pin "45") (pinfunction "PC5_45") (pintype "bidirectional"))
    )
    (net (code "70") (name "unconnected-(IC1A-PC6-Pad96)") (class "Default")
      (node (ref "IC1") (pin "96") (pinfunction "PC6_96") (pintype "bidirectional"))
    )
    (net (code "71") (name "unconnected-(IC1A-PC7-Pad97)") (class "Default")
      (node (ref "IC1") (pin "97") (pinfunction "PC7_97") (pintype "bidirectional"))
    )
    (net (code "72") (name "unconnected-(IC1A-PC8-Pad98)") (class "Default")
      (node (ref "IC1") (pin "98") (pinfunction "PC8_98") (pintype "bidirectional"))
    )
    (net (code "73") (name "unconnected-(IC1A-PC9-Pad99)") (class "Default")
      (node (ref "IC1") (pin "99") (pinfunction "PC9_99") (pintype "bidirectional"))
    )
    (net (code "74") (name "unconnected-(IC1A-PC10-Pad111)") (class "Default")
      (node (ref "IC1") (pin "111") (pinfunction "PC10_111") (pintype "bidirectional"))
    )
    (net (code "75") (name "unconnected-(IC1A-PC11-Pad112)") (class "Default")
      (node (ref "IC1") (pin "112") (pinfunction "PC11_112") (pintype "bidirectional"))
    )
    (net (code "76") (name "unconnected-(IC1A-PC12-Pad113)") (class "Default")
      (node (ref "IC1") (pin "113") (pinfunction "PC12_113") (pintype "bidirectional"))
    )
    (net (code "77") (name "unconnected-(IC1A-PC13-Pad7)") (class "Default")
      (node (ref "IC1") (pin "7") (pinfunction "PC13_7") (pintype "bidirectional"))
    )
    (net (code "78") (name "unconnected-(IC1A-PC14-Pad8)") (class "Default")
      (node (ref "IC1") (pin "8") (pinfunction "PC14_8") (pintype "bidirectional"))
    )
    (net (code "79") (name "unconnected-(IC1A-PC15-Pad9)") (class "Default")
      (node (ref "IC1") (pin "9") (pinfunction "PC15_9") (pintype "bidirectional"))
    )
    (net (code "80") (name "unconnected-(IC1A-PD0-Pad114)") (class "Default")
      (node (ref "IC1") (pin "114") (pinfunction "PD0_114") (pintype "bidirectional"))
    )
    (net (code "81") (name "unconnected-(IC1A-PD1-Pad115)") (class "Default")
      (node (ref "IC1") (pin "115") (pinfunction "PD1_115") (pintype "bidirectional"))
    )
    (net (code "82") (name "unconnected-(IC1A-PD2-Pad116)") (class "Default")
      (node (ref "IC1") (pin "116") (pinfunction "PD2_116") (pintype "bidirectional"))
    )
    (net (code "83") (name "unconnected-(IC1A-PD3-Pad117)") (class "Default")
      (node (ref "IC1") (pin "117") (pinfunction "PD3_117") (pintype "bidirectional"))
    )
    (net (code "84") (name "unconnected-(IC1A-PD4-Pad118)") (class "Default")
      (node (ref "IC1") (pin "118") (pinfunction "PD4_118") (pintype "bidirectional"))
    )
    (net (code "85") (name "unconnected-(IC1A-PD5-Pad119)") (class "Default")
      (node (ref "IC1") (pin "119") (pinfunction "PD5_119") (pintype "bidirectional"))
    )
    (net (code "86") (name "unconnected-(IC1A-PD6-Pad122)") (class "Default")
      (node (ref "IC1") (pin "122") (pinfunction "PD6_122") (pintype "bidirectional"))
    )
    (net (code "87") (name "unconnected-(IC1A-PD7-Pad123)") (class "Default")
      (node (ref "IC1") (pin "123") (pinfunction "PD7_123") (pintype "bidirectional"))
    )
    (net (code "88") (name "unconnected-(IC1A-PD8-Pad77)") (class "Default")
      (node (ref "IC1") (pin "77") (pinfunction "PD8_77") (pintype "bidirectional"))
    )
    (net (code "89") (name "unconnected-(IC1A-PD9-Pad78)") (class "Default")
      (node (ref "IC1") (pin "78") (pinfunction "PD9_78") (pintype "bidirectional"))
    )
    (net (code "90") (name "unconnected-(IC1A-PD10-Pad79)") (class "Default")
      (node (ref "IC1") (pin "79") (pinfunction "PD10_79") (pintype "bidirectional"))
    )
    (net (code "91") (name "unconnected-(IC1A-PD11-Pad80)") (class "Default")
      (node (ref "IC1") (pin "80") (pinfunction "PD11_80") (pintype "bidirectional"))
    )
    (net (code "92") (name "unconnected-(IC1A-PD12-Pad81)") (class "Default")
      (node (ref "IC1") (pin "81") (pinfunction "PD12_81") (pintype "bidirectional"))
    )
    (net (code "93") (name "unconnected-(IC1A-PD13-Pad82)") (class "Default")
      (node (ref "IC1") (pin "82") (pinfunction "PD13_82") (pintype "bidirectional"))
    )
    (net (code "94") (name "unconnected-(IC1A-PD14-Pad85)") (class "Default")
      (node (ref "IC1") (pin "85") (pinfunction "PD14_85") (pintype "bidirectional"))
    )
    (net (code "95") (name "unconnected-(IC1A-PD15-Pad86)") (class "Default")
      (node (ref "IC1") (pin "86") (pinfunction "PD15_86") (pintype "bidirectional"))
    )
    (net (code "96") (name "unconnected-(IC1A-PE0-Pad141)") (class "Default")
      (node (ref "IC1") (pin "141") (pinfunction "PE0_141") (pintype "bidirectional"))
    )
    (net (code "97") (name "unconnected-(IC1A-PE1-Pad142)") (class "Default")
      (node (ref "IC1") (pin "142") (pinfunction "PE1_142") (pintype "bidirectional"))
    )
    (net (code "98") (name "unconnected-(IC1A-PE2-Pad1)") (class "Default")
      (node (ref "IC1") (pin "1") (pinfunction "PE2_1") (pintype "bidirectional"))
    )
    (net (code "99") (name "unconnected-(IC1A-PE3-Pad2)") (class "Default")
      (node (ref "IC1") (pin "2") (pinfunction "PE3_2") (pintype "bidirectional"))
    )
    (net (code "100") (name "unconnected-(IC1A-PE4-Pad3)") (class "Default")
      (node (ref "IC1") (pin "3") (pinfunction "PE4_3") (pintype "bidirectional"))
    )
    (net (code "101") (name "unconnected-(IC1A-PE5-Pad4)") (class "Default")
      (node (ref "IC1") (pin "4") (pinfunction "PE5_4") (pintype "bidirectional"))
    )
    (net (code "102") (name "unconnected-(IC1A-PE6-Pad5)") (class "Default")
      (node (ref "IC1") (pin "5") (pinfunction "PE6_5") (pintype "bidirectional"))
    )
    (net (code "103") (name "unconnected-(IC1A-PE7-Pad58)") (class "Default")
      (node (ref "IC1") (pin "58") (pinfunction "PE7_58") (pintype "bidirectional"))
    )
    (net (code "104") (name "unconnected-(IC1A-PE8-Pad59)") (class "Default")
      (node (ref "IC1") (pin "59") (pinfunction "PE8_59") (pintype "bidirectional"))
    )
    (net (code "105") (name "unconnected-(IC1A-PE9-Pad60)") (class "Default")
      (node (ref "IC1") (pin "60") (pinfunction "PE9_60") (pintype "bidirectional"))
    )
    (net (code "106") (name "unconnected-(IC1A-PE10-Pad63)") (class "Default")
      (node (ref "IC1") (pin "63") (pinfunction "PE10_63") (pintype "bidirectional"))
    )
    (net (code "107") (name "unconnected-(IC1A-PE11-Pad64)") (class "Default")
      (node (ref "IC1") (pin "64") (pinfunction "PE11_64") (pintype "bidirectional"))
    )
    (net (code "108") (name "unconnected-(IC1A-PE13-Pad66)") (class "Default")
      (node (ref "IC1") (pin "66") (pinfunction "PE13_66") (pintype "bidirectional"))
    )
    (net (code "109") (name "unconnected-(IC1A-PE14-Pad67)") (class "Default")
      (node (ref "IC1") (pin "67") (pinfunction "PE14_67") (pintype "bidirectional"))
    )
    (net (code "110") (name "unconnected-(IC1A-PE15-Pad68)") (class "Default")
      (node (ref "IC1") (pin "68") (pinfunction "PE15_68") (pintype "bidirectional"))
    )
    (net (code "111") (name "unconnected-(IC1A-PF0-Pad10)") (class "Default")
      (node (ref "IC1") (pin "10") (pinfunction "PF0_10") (pintype "bidirectional"))
    )
    (net (code "112") (name "unconnected-(IC1A-PF1-Pad11)") (class "Default")
      (node (ref "IC1") (pin "11") (pinfunction "PF1_11") (pintype "bidirectional"))
    )
    (net (code "113") (name "unconnected-(IC1A-PF2-Pad12)") (class "Default")
      (node (ref "IC1") (pin "12") (pinfunction "PF2_12") (pintype "bidirectional"))
    )
    (net (code "114") (name "unconnected-(IC1A-PF3-Pad13)") (class "Default")
      (node (ref "IC1") (pin "13") (pinfunction "PF3_13") (pintype "bidirectional"))
    )
    (net (code "115") (name "unconnected-(IC1A-PF4-Pad14)") (class "Default")
      (node (ref "IC1") (pin "14") (pinfunction "PF4_14") (pintype "bidirectional"))
    )
    (net (code "116") (name "unconnected-(IC1A-PF5-Pad15)") (class "Default")
      (node (ref "IC1") (pin "15") (pinfunction "PF5_15") (pintype "bidirectional"))
    )
    (net (code "117") (name "unconnected-(IC1A-PF6-Pad18)") (class "Default")
      (node (ref "IC1") (pin "18") (pinfunction "PF6_18") (pintype "bidirectional"))
    )
    (net (code "118") (name "unconnected-(IC1A-PF7-Pad19)") (class "Default")
      (node (ref "IC1") (pin "19") (pinfunction "PF7_19") (pintype "bidirectional"))
    )
    (net (code "119") (name "unconnected-(IC1A-PF8-Pad20)") (class "Default")
      (node (ref "IC1") (pin "20") (pinfunction "PF8_20") (pintype "bidirectional"))
    )
    (net (code "120") (name "unconnected-(IC1A-PF11-Pad49)") (class "Default")
      (node (ref "IC1") (pin "49") (pinfunction "PF11_49") (pintype "bidirectional"))
    )
    (net (code "121") (name "unconnected-(IC1A-PF12-Pad50)") (class "Default")
      (node (ref "IC1") (pin "50") (pinfunction "PF12_50") (pintype "bidirectional"))
    )
    (net (code "122") (name "unconnected-(IC1A-PF13-Pad53)") (class "Default")
      (node (ref "IC1") (pin "53") (pinfunction "PF13_53") (pintype "bidirectional"))
    )
    (net (code "123") (name "unconnected-(IC1A-PF14-Pad54)") (class "Default")
      (node (ref "IC1") (pin "54") (pinfunction "PF14_54") (pintype "bidirectional"))
    )
    (net (code "124") (name "unconnected-(IC1A-PF15-Pad55)") (class "Default")
      (node (ref "IC1") (pin "55") (pinfunction "PF15_55") (pintype "bidirectional"))
    )
    (net (code "125") (name "unconnected-(IC1A-PG0-Pad56)") (class "Default")
      (node (ref "IC1") (pin "56") (pinfunction "PG0_56") (pintype "bidirectional"))
    )
    (net (code "126") (name "unconnected-(IC1A-PG1-Pad57)") (class "Default")
      (node (ref "IC1") (pin "57") (pinfunction "PG1_57") (pintype "bidirectional"))
    )
    (net (code "127") (name "unconnected-(IC1A-PG2-Pad87)") (class "Default")
      (node (ref "IC1") (pin "87") (pinfunction "PG2_87") (pintype "bidirectional"))
    )
    (net (code "128") (name "unconnected-(IC1A-PG3-Pad88)") (class "Default")
      (node (ref "IC1") (pin "88") (pinfunction "PG3_88") (pintype "bidirectional"))
    )
    (net (code "129") (name "unconnected-(IC1A-PG4-Pad89)") (class "Default")
      (node (ref "IC1") (pin "89") (pinfunction "PG4_89") (pintype "bidirectional"))
    )
    (net (code "130") (name "unconnected-(IC1A-PG5-Pad90)") (class "Default")
      (node (ref "IC1") (pin "90") (pinfunction "PG5_90") (pintype "bidirectional"))
    )
    (net (code "131") (name "unconnected-(IC1A-PG6-Pad91)") (class "Default")
      (node (ref "IC1") (pin "91") (pinfunction "PG6_91") (pintype "bidirectional"))
    )
    (net (code "132") (name "unconnected-(IC1A-PG7-Pad92)") (class "Default")
      (node (ref "IC1") (pin "92") (pinfunction "PG7_92") (pintype "bidirectional"))
    )
    (net (code "133") (name "unconnected-(IC1A-PG8-Pad93)") (class "Default")
      (node (ref "IC1") (pin "93") (pinfunction "PG8_93") (pintype "bidirectional"))
    )
    (net (code "134") (name "unconnected-(IC1A-PG9-Pad124)") (class "Default")
      (node (ref "IC1") (pin "124") (pinfunction "PG9_124") (pintype "bidirectional"))
    )
    (net (code "135") (name "unconnected-(IC1A-PG10-Pad125)") (class "Default")
      (node (ref "IC1") (pin "125") (pinfunction "PG10_125") (pintype "bidirectional"))
    )
    (net (code "136") (name "unconnected-(IC1A-PG11-Pad126)") (class "Default")
      (node (ref "IC1") (pin "126") (pinfunction "PG11_126") (pintype "bidirectional"))
    )
    (net (code "137") (name "unconnected-(IC1A-PG12-Pad127)") (class "Default")
      (node (ref "IC1") (pin "127") (pinfunction "PG12_127") (pintype "bidirectional"))
    )
    (net (code "138") (name "unconnected-(IC1A-PG13-Pad128)") (class "Default")
      (node (ref "IC1") (pin "128") (pinfunction "PG13_128") (pintype "bidirectional"))
    )
    (net (code "139") (name "unconnected-(IC1A-PG14-Pad129)") (class "Default")
      (node (ref "IC1") (pin "129") (pinfunction "PG14_129") (pintype "bidirectional"))
    )
    (net (code "140") (name "unconnected-(IC1A-PG15-Pad132)") (class "Default")
      (node (ref "IC1") (pin "132") (pinfunction "PG15_132") (pintype "bidirectional"))
    )
    (net (code "141") (name "unconnected-(RT9013-1-NC-Pad4)") (class "Default")
      (node (ref "RT9013-1") (pin "4") (pinfunction "NC_4") (pintype "bidirectional"))
    )
    (net (code "142") (name "unconnected-(SW-1-B-PadP$1)") (class "Default")
      (node (ref "SW-1") (pin "P$1") (pinfunction "B_P$1") (pintype "bidirectional"))
    )
    (net (code "143") (name "unconnected-(SW3P-2-COM-Pad3)") (class "Default")
      (node (ref "SW3P-2") (pin "3") (pinfunction "COM_3") (pintype "bidirectional"))
    )
    (net (code "144") (name "unconnected-(USB2-ID-Pad4)") (class "Default")
      (node (ref "USB2") (pin "4") (pinfunction "ID_4") (pintype "bidirectional"))
    )
    (net (code "145") (name "unconnected-(Y1-1-Pad4)") (class "Default")
      (node (ref "Y1") (pin "4") (pinfunction "1_4") (pintype "bidirectional"))
    )
    (net (code "146") (name "unconnected-(Y1-3-Pad2)") (class "Default")
      (node (ref "Y1") (pin "2") (pinfunction "3_2") (pintype "bidirectional"))
    )
  )
)
